# serial_plotter_easyEDA.net
KiCad netlist of a schematic drawn in EasyEDA
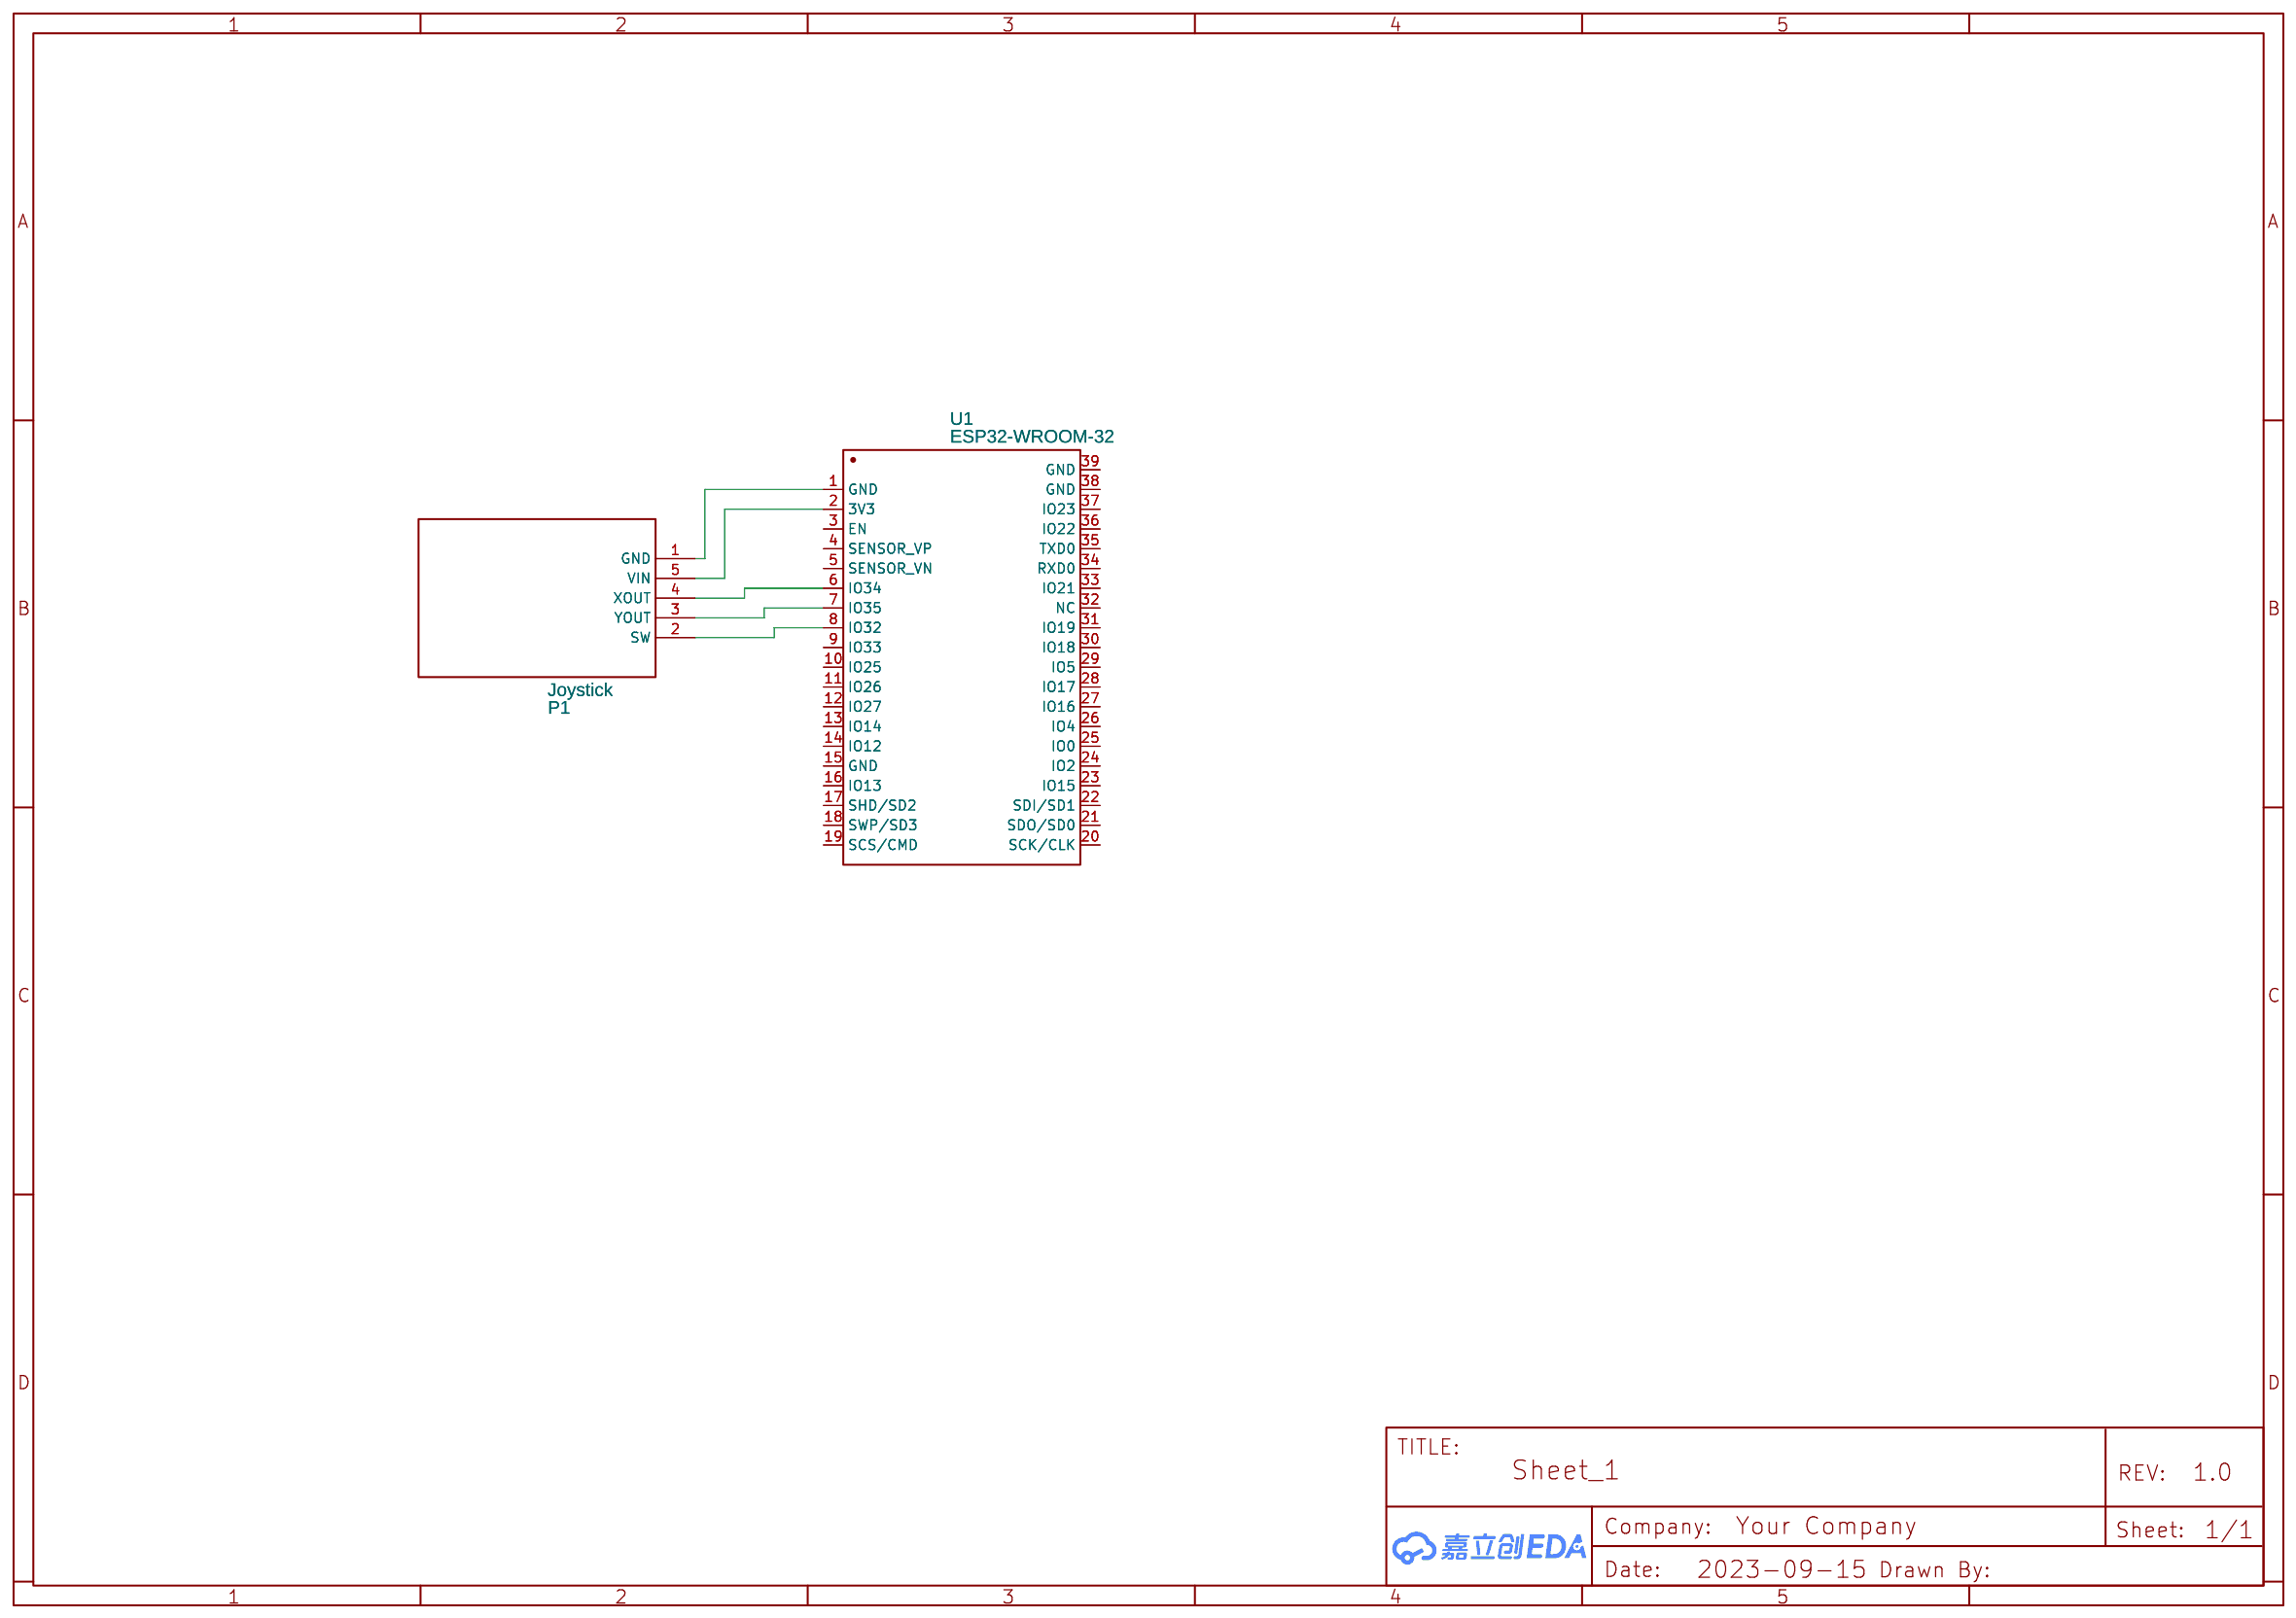
[diagram p0: schematic sheet]

(export (version "E")
  (design (tool "Eeschema 10.0.6"))
  (components
    (comp (ref "P1") (value "Joystick") (libsource (lib "") (part "Joystick")))
    (comp (ref "U1")
      (value "ESP32-WROOM-32")
      (fields
        (field (name "Manufacturer Part") "ESP32-WROOM-32-N4")
        (field (name "Manufacturer") "ESPRESSIF(乐鑫)")
      )
      (libsource (lib "") (part "ESP32-WROOM-32"))
    )
  )
  (nets
    (net (code "1") (name "Net-(P1-GND)") (class "Default")
      (node (ref "P1") (pin "1") (pinfunction "GND_1") (pintype "unspecified"))
      (node (ref "U1") (pin "1") (pinfunction "GND_1") (pintype "unspecified"))
    )
    (net (code "2") (name "Net-(P1-SW)") (class "Default")
      (node (ref "P1") (pin "2") (pinfunction "SW_2") (pintype "unspecified"))
      (node (ref "U1") (pin "8") (pinfunction "IO32_8") (pintype "unspecified"))
    )
    (net (code "3") (name "Net-(P1-VIN)") (class "Default")
      (node (ref "P1") (pin "5") (pinfunction "VIN_5") (pintype "unspecified"))
      (node (ref "U1") (pin "2") (pinfunction "3V3_2") (pintype "unspecified"))
    )
    (net (code "4") (name "Net-(P1-XOUT)") (class "Default")
      (node (ref "P1") (pin "4") (pinfunction "XOUT_4") (pintype "unspecified"))
      (node (ref "U1") (pin "6") (pinfunction "IO34_6") (pintype "unspecified"))
    )
    (net (code "5") (name "Net-(P1-YOUT)") (class "Default")
      (node (ref "P1") (pin "3") (pinfunction "YOUT_3") (pintype "unspecified"))
      (node (ref "U1") (pin "7") (pinfunction "IO35_7") (pintype "unspecified"))
    )
    (net (code "6") (name "unconnected-(U1-EN-Pad3)") (class "Default")
      (node (ref "U1") (pin "3") (pinfunction "EN_3") (pintype "unspecified"))
    )
    (net (code "7") (name "unconnected-(U1-GND-Pad15)") (class "Default")
      (node (ref "U1") (pin "15") (pinfunction "GND_15") (pintype "unspecified"))
    )
    (net (code "8") (name "unconnected-(U1-GND-Pad38)") (class "Default")
      (node (ref "U1") (pin "38") (pinfunction "GND_38") (pintype "unspecified"))
    )
    (net (code "9") (name "unconnected-(U1-GND-Pad39)") (class "Default")
      (node (ref "U1") (pin "39") (pinfunction "GND_39") (pintype "unspecified"))
    )
    (net (code "10") (name "unconnected-(U1-IO0-Pad25)") (class "Default")
      (node (ref "U1") (pin "25") (pinfunction "IO0_25") (pintype "unspecified"))
    )
    (net (code "11") (name "unconnected-(U1-IO2-Pad24)") (class "Default")
      (node (ref "U1") (pin "24") (pinfunction "IO2_24") (pintype "unspecified"))
    )
    (net (code "12") (name "unconnected-(U1-IO4-Pad26)") (class "Default")
      (node (ref "U1") (pin "26") (pinfunction "IO4_26") (pintype "unspecified"))
    )
    (net (code "13") (name "unconnected-(U1-IO5-Pad29)") (class "Default")
      (node (ref "U1") (pin "29") (pinfunction "IO5_29") (pintype "unspecified"))
    )
    (net (code "14") (name "unconnected-(U1-IO12-Pad14)") (class "Default")
      (node (ref "U1") (pin "14") (pinfunction "IO12_14") (pintype "unspecified"))
    )
    (net (code "15") (name "unconnected-(U1-IO13-Pad16)") (class "Default")
      (node (ref "U1") (pin "16") (pinfunction "IO13_16") (pintype "unspecified"))
    )
    (net (code "16") (name "unconnected-(U1-IO14-Pad13)") (class "Default")
      (node (ref "U1") (pin "13") (pinfunction "IO14_13") (pintype "unspecified"))
    )
    (net (code "17") (name "unconnected-(U1-IO15-Pad23)") (class "Default")
      (node (ref "U1") (pin "23") (pinfunction "IO15_23") (pintype "unspecified"))
    )
    (net (code "18") (name "unconnected-(U1-IO16-Pad27)") (class "Default")
      (node (ref "U1") (pin "27") (pinfunction "IO16_27") (pintype "unspecified"))
    )
    (net (code "19") (name "unconnected-(U1-IO17-Pad28)") (class "Default")
      (node (ref "U1") (pin "28") (pinfunction "IO17_28") (pintype "unspecified"))
    )
    (net (code "20") (name "unconnected-(U1-IO18-Pad30)") (class "Default")
      (node (ref "U1") (pin "30") (pinfunction "IO18_30") (pintype "unspecified"))
    )
    (net (code "21") (name "unconnected-(U1-IO19-Pad31)") (class "Default")
      (node (ref "U1") (pin "31") (pinfunction "IO19_31") (pintype "unspecified"))
    )
    (net (code "22") (name "unconnected-(U1-IO21-Pad33)") (class "Default")
      (node (ref "U1") (pin "33") (pinfunction "IO21_33") (pintype "unspecified"))
    )
    (net (code "23") (name "unconnected-(U1-IO22-Pad36)") (class "Default")
      (node (ref "U1") (pin "36") (pinfunction "IO22_36") (pintype "unspecified"))
    )
    (net (code "24") (name "unconnected-(U1-IO23-Pad37)") (class "Default")
      (node (ref "U1") (pin "37") (pinfunction "IO23_37") (pintype "unspecified"))
    )
    (net (code "25") (name "unconnected-(U1-IO25-Pad10)") (class "Default")
      (node (ref "U1") (pin "10") (pinfunction "IO25_10") (pintype "unspecified"))
    )
    (net (code "26") (name "unconnected-(U1-IO26-Pad11)") (class "Default")
      (node (ref "U1") (pin "11") (pinfunction "IO26_11") (pintype "unspecified"))
    )
    (net (code "27") (name "unconnected-(U1-IO27-Pad12)") (class "Default")
      (node (ref "U1") (pin "12") (pinfunction "IO27_12") (pintype "unspecified"))
    )
    (net (code "28") (name "unconnected-(U1-IO33-Pad9)") (class "Default")
      (node (ref "U1") (pin "9") (pinfunction "IO33_9") (pintype "unspecified"))
    )
    (net (code "29") (name "unconnected-(U1-NC-Pad32)") (class "Default")
      (node (ref "U1") (pin "32") (pinfunction "NC_32") (pintype "unspecified"))
    )
    (net (code "30") (name "unconnected-(U1-RXD0-Pad34)") (class "Default")
      (node (ref "U1") (pin "34") (pinfunction "RXD0_34") (pintype "unspecified"))
    )
    (net (code "31") (name "unconnected-(U1-SCK{slash}CLK-Pad20)") (class "Default")
      (node (ref "U1") (pin "20") (pinfunction "SCK/CLK_20") (pintype "unspecified"))
    )
    (net (code "32") (name "unconnected-(U1-SCS{slash}CMD-Pad19)") (class "Default")
      (node (ref "U1") (pin "19") (pinfunction "SCS/CMD_19") (pintype "unspecified"))
    )
    (net (code "33") (name "unconnected-(U1-SDI{slash}SD1-Pad22)") (class "Default")
      (node (ref "U1") (pin "22") (pinfunction "SDI/SD1_22") (pintype "unspecified"))
    )
    (net (code "34") (name "unconnected-(U1-SDO{slash}SD0-Pad21)") (class "Default")
      (node (ref "U1") (pin "21") (pinfunction "SDO/SD0_21") (pintype "unspecified"))
    )
    (net (code "35") (name "unconnected-(U1-SENSOR_VN-Pad5)") (class "Default")
      (node (ref "U1") (pin "5") (pinfunction "SENSOR_VN_5") (pintype "unspecified"))
    )
    (net (code "36") (name "unconnected-(U1-SENSOR_VP-Pad4)") (class "Default")
      (node (ref "U1") (pin "4") (pinfunction "SENSOR_VP_4") (pintype "unspecified"))
    )
    (net (code "37") (name "unconnected-(U1-SHD{slash}SD2-Pad17)") (class "Default")
      (node (ref "U1") (pin "17") (pinfunction "SHD/SD2_17") (pintype "unspecified"))
    )
    (net (code "38") (name "unconnected-(U1-SWP{slash}SD3-Pad18)") (class "Default")
      (node (ref "U1") (pin "18") (pinfunction "SWP/SD3_18") (pintype "unspecified"))
    )
    (net (code "39") (name "unconnected-(U1-TXD0-Pad35)") (class "Default")
      (node (ref "U1") (pin "35") (pinfunction "TXD0_35") (pintype "unspecified"))
    )
  )
)
